# motor_controlboard.net
KiCad netlist of a schematic drawn in EAGLE
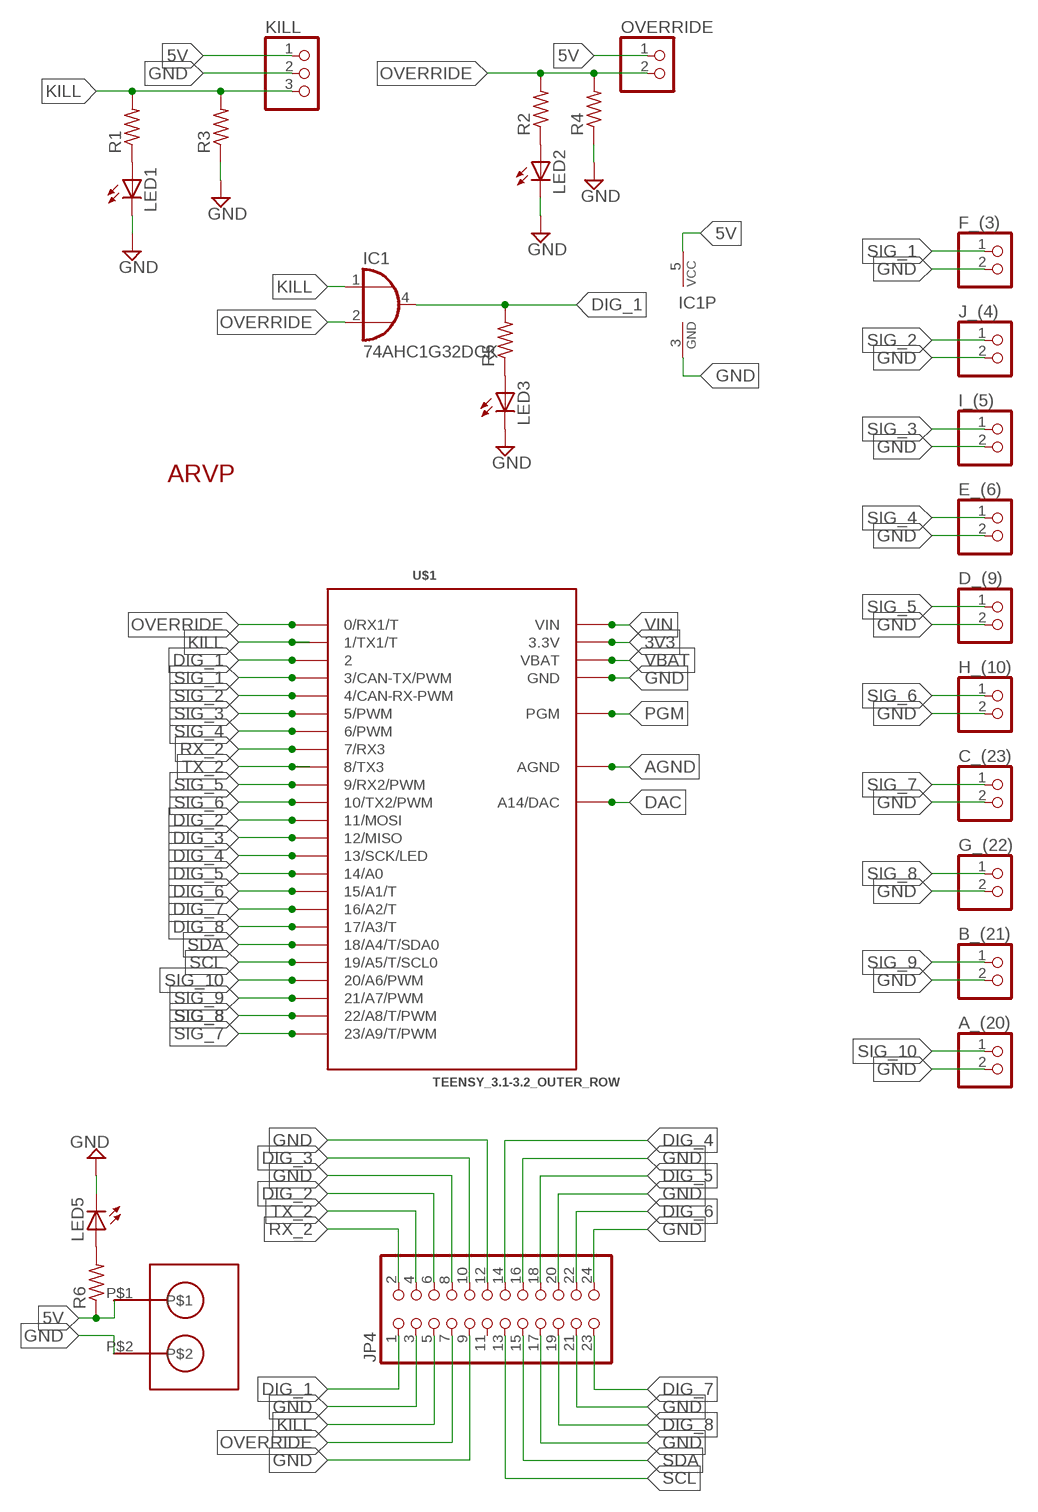
[diagram p0: schematic, sheet 1]

(export (version "E")
  (design (tool "Eeschema 10.0.6"))
  (components
    (comp (ref "A_(20)")
      (value "PINHD-1X2")
      (footprint "eagle-import:1X02")
      (libsource (lib "eagle-import") (part "PINHD-1X2"))
    )
    (comp (ref "B_(21)")
      (value "PINHD-1X2")
      (footprint "eagle-import:1X02")
      (libsource (lib "eagle-import") (part "PINHD-1X2"))
    )
    (comp (ref "C_(23)")
      (value "PINHD-1X2")
      (footprint "eagle-import:1X02")
      (libsource (lib "eagle-import") (part "PINHD-1X2"))
    )
    (comp (ref "D_(9)")
      (value "PINHD-1X2")
      (footprint "eagle-import:1X02")
      (libsource (lib "eagle-import") (part "PINHD-1X2"))
    )
    (comp (ref "E_(6)")
      (value "PINHD-1X2")
      (footprint "eagle-import:1X02")
      (libsource (lib "eagle-import") (part "PINHD-1X2"))
    )
    (comp (ref "F_(3)")
      (value "PINHD-1X2")
      (footprint "eagle-import:1X02")
      (libsource (lib "eagle-import") (part "PINHD-1X2"))
    )
    (comp (ref "G_(22)")
      (value "PINHD-1X2")
      (footprint "eagle-import:1X02")
      (libsource (lib "eagle-import") (part "PINHD-1X2"))
    )
    (comp (ref "H_(10)")
      (value "PINHD-1X2")
      (footprint "eagle-import:1X02")
      (libsource (lib "eagle-import") (part "PINHD-1X2"))
    )
    (comp (ref "IC1")
      (value "74AHC1G32DCK")
      (footprint "eagle-import:SC70-5")
      (libsource (lib "eagle-import") (part "741G32DCKAHC"))
    )
    (comp (ref "I_(5)")
      (value "PINHD-1X2")
      (footprint "eagle-import:1X02")
      (libsource (lib "eagle-import") (part "PINHD-1X2"))
    )
    (comp (ref "JP4")
      (value "PINHD-2X12")
      (footprint "eagle-import:2X12")
      (libsource (lib "eagle-import") (part "PINHD-2X12"))
    )
    (comp (ref "J_(4)")
      (value "PINHD-1X2")
      (footprint "eagle-import:1X02")
      (libsource (lib "eagle-import") (part "PINHD-1X2"))
    )
    (comp (ref "KILL")
      (value "PINHD-1X3")
      (footprint "eagle-import:1X03")
      (libsource (lib "eagle-import") (part "PINHD-1X3"))
    )
    (comp (ref "LED1")
      (value "LEDCHIP-LED0805")
      (footprint "eagle-import:CHIP-LED0805")
      (libsource (lib "eagle-import") (part "LEDCHIP-LED0805"))
    )
    (comp (ref "LED2")
      (value "LEDCHIP-LED0805")
      (footprint "eagle-import:CHIP-LED0805")
      (libsource (lib "eagle-import") (part "LEDCHIP-LED0805"))
    )
    (comp (ref "LED3")
      (value "LEDCHIP-LED0805")
      (footprint "eagle-import:CHIP-LED0805")
      (libsource (lib "eagle-import") (part "LEDCHIP-LED0805"))
    )
    (comp (ref "LED5")
      (value "LEDCHIP-LED0805")
      (footprint "eagle-import:CHIP-LED0805")
      (libsource (lib "eagle-import") (part "LEDCHIP-LED0805"))
    )
    (comp (ref "OVERRIDE")
      (value "PINHD-1X2")
      (footprint "eagle-import:1X02")
      (libsource (lib "eagle-import") (part "PINHD-1X2"))
    )
    (comp (ref "R1")
      (value "R-US_R0805")
      (footprint "eagle-import:R0805")
      (libsource (lib "eagle-import") (part "R-US_R0805"))
    )
    (comp (ref "R2")
      (value "R-US_R0805")
      (footprint "eagle-import:R0805")
      (libsource (lib "eagle-import") (part "R-US_R0805"))
    )
    (comp (ref "R3")
      (value "R-US_R0805")
      (footprint "eagle-import:R0805")
      (libsource (lib "eagle-import") (part "R-US_R0805"))
    )
    (comp (ref "R4")
      (value "R-US_R0805")
      (footprint "eagle-import:R0805")
      (libsource (lib "eagle-import") (part "R-US_R0805"))
    )
    (comp (ref "R5")
      (value "R-US_R0805")
      (footprint "eagle-import:R0805")
      (libsource (lib "eagle-import") (part "R-US_R0805"))
    )
    (comp (ref "R6")
      (value "R-US_R0805")
      (footprint "eagle-import:R0805")
      (libsource (lib "eagle-import") (part "R-US_R0805"))
    )
    (comp (ref "U$1")
      (value "TEENSY_3.1-3.2_OUTER_ROW")
      (footprint "eagle-import:TEENSY_3.0-3.2&LC_OUTER_ROW")
      (libsource (lib "eagle-import") (part "TEENSY_3.1-3.2_OUTER_ROW"))
    )
    (comp (ref "U$2")
      (value "ARVP_LOGO")
      (footprint "eagle-import:ARVP")
      (libsource (lib "eagle-import") (part "ARVP_LOGO"))
    )
    (comp (ref "U$3")
      (value "ARVP_MOLEX_FEMALE")
      (footprint "eagle-import:ARVP_MOLEX_FEMALE")
      (libsource (lib "eagle-import") (part "ARVP_MOLEX_FEMALE"))
    )
  )
  (nets
    (net (code "1") (name "3V3") (class "Default")
      (node (ref "U$1") (pin "3.3V") (pinfunction "3.3V_3.3V") (pintype "power_in"))
      (node (ref "U$1") (pin "3.3V1") (pinfunction "3.3V_3.3V1") (pintype "power_in"))
    )
    (net (code "2") (name "5V") (class "Default")
      (node (ref "IC1") (pin "5") (pinfunction "VCC_5") (pintype "power_in"))
      (node (ref "KILL") (pin "1") (pinfunction "1_1") (pintype "passive"))
      (node (ref "OVERRIDE") (pin "1") (pinfunction "1_1") (pintype "passive"))
      (node (ref "R6") (pin "1") (pinfunction "1_1") (pintype "passive"))
      (node (ref "U$3") (pin "P$1") (pinfunction "P$1_P$1") (pintype "bidirectional"))
    )
    (net (code "3") (name "AGND") (class "Default")
      (node (ref "U$1") (pin "AGND") (pinfunction "AGND_AGND") (pintype "power_in"))
    )
    (net (code "4") (name "DAC") (class "Default")
      (node (ref "U$1") (pin "RESET/DAC") (pinfunction "A14/DAC_RESET/DAC") (pintype "bidirectional"))
    )
    (net (code "5") (name "DIG_1") (class "Default")
      (node (ref "IC1") (pin "4") (pinfunction "O_4") (pintype "output"))
      (node (ref "JP4") (pin "1") (pinfunction "1_1") (pintype "passive"))
      (node (ref "R5") (pin "2") (pinfunction "2_2") (pintype "passive"))
      (node (ref "U$1") (pin "2") (pinfunction "2_2") (pintype "bidirectional"))
    )
    (net (code "6") (name "DIG_2") (class "Default")
      (node (ref "JP4") (pin "6") (pinfunction "6_6") (pintype "passive"))
      (node (ref "U$1") (pin "11") (pinfunction "11/MOSI_11") (pintype "bidirectional"))
    )
    (net (code "7") (name "DIG_3") (class "Default")
      (node (ref "JP4") (pin "10") (pinfunction "10_10") (pintype "passive"))
      (node (ref "U$1") (pin "12") (pinfunction "12/MISO_12") (pintype "bidirectional"))
    )
    (net (code "8") (name "DIG_4") (class "Default")
      (node (ref "JP4") (pin "14") (pinfunction "14_14") (pintype "passive"))
      (node (ref "U$1") (pin "13") (pinfunction "13/SCK/LED_13") (pintype "bidirectional"))
    )
    (net (code "9") (name "DIG_5") (class "Default")
      (node (ref "JP4") (pin "18") (pinfunction "18_18") (pintype "passive"))
      (node (ref "U$1") (pin "14/A0") (pinfunction "14/A0_14/A0") (pintype "bidirectional"))
    )
    (net (code "10") (name "DIG_6") (class "Default")
      (node (ref "JP4") (pin "22") (pinfunction "22_22") (pintype "passive"))
      (node (ref "U$1") (pin "15/A1") (pinfunction "15/A1/T_15/A1") (pintype "bidirectional"))
    )
    (net (code "11") (name "DIG_7") (class "Default")
      (node (ref "JP4") (pin "23") (pinfunction "23_23") (pintype "passive"))
      (node (ref "U$1") (pin "16/A2") (pinfunction "16/A2/T_16/A2") (pintype "bidirectional"))
    )
    (net (code "12") (name "DIG_8") (class "Default")
      (node (ref "JP4") (pin "19") (pinfunction "19_19") (pintype "passive"))
      (node (ref "U$1") (pin "17/A3") (pinfunction "17/A3/T_17/A3") (pintype "bidirectional"))
    )
    (net (code "13") (name "GND") (class "Default")
      (node (ref "A_(20)") (pin "2") (pinfunction "2_2") (pintype "passive"))
      (node (ref "B_(21)") (pin "2") (pinfunction "2_2") (pintype "passive"))
      (node (ref "C_(23)") (pin "2") (pinfunction "2_2") (pintype "passive"))
      (node (ref "D_(9)") (pin "2") (pinfunction "2_2") (pintype "passive"))
      (node (ref "E_(6)") (pin "2") (pinfunction "2_2") (pintype "passive"))
      (node (ref "F_(3)") (pin "2") (pinfunction "2_2") (pintype "passive"))
      (node (ref "G_(22)") (pin "2") (pinfunction "2_2") (pintype "passive"))
      (node (ref "H_(10)") (pin "2") (pinfunction "2_2") (pintype "passive"))
      (node (ref "IC1") (pin "3") (pinfunction "GND_3") (pintype "power_in"))
      (node (ref "I_(5)") (pin "2") (pinfunction "2_2") (pintype "passive"))
      (node (ref "JP4") (pin "12") (pinfunction "12_12") (pintype "passive"))
      (node (ref "JP4") (pin "16") (pinfunction "16_16") (pintype "passive"))
      (node (ref "JP4") (pin "17") (pinfunction "17_17") (pintype "passive"))
      (node (ref "JP4") (pin "20") (pinfunction "20_20") (pintype "passive"))
      (node (ref "JP4") (pin "21") (pinfunction "21_21") (pintype "passive"))
      (node (ref "JP4") (pin "24") (pinfunction "24_24") (pintype "passive"))
      (node (ref "JP4") (pin "3") (pinfunction "3_3") (pintype "passive"))
      (node (ref "JP4") (pin "8") (pinfunction "8_8") (pintype "passive"))
      (node (ref "JP4") (pin "9") (pinfunction "9_9") (pintype "passive"))
      (node (ref "J_(4)") (pin "2") (pinfunction "2_2") (pintype "passive"))
      (node (ref "KILL") (pin "2") (pinfunction "2_2") (pintype "passive"))
      (node (ref "LED1") (pin "C") (pinfunction "C_C") (pintype "passive"))
      (node (ref "LED2") (pin "C") (pinfunction "C_C") (pintype "passive"))
      (node (ref "LED3") (pin "C") (pinfunction "C_C") (pintype "passive"))
      (node (ref "LED5") (pin "C") (pinfunction "C_C") (pintype "passive"))
      (node (ref "R3") (pin "1") (pinfunction "1_1") (pintype "passive"))
      (node (ref "R4") (pin "1") (pinfunction "1_1") (pintype "passive"))
      (node (ref "U$1") (pin "GND") (pinfunction "GND_GND") (pintype "power_in"))
      (node (ref "U$1") (pin "GND1") (pinfunction "GND_GND1") (pintype "power_in"))
      (node (ref "U$3") (pin "P$2") (pinfunction "P$2_P$2") (pintype "bidirectional"))
    )
    (net (code "14") (name "KILL") (class "Default")
      (node (ref "IC1") (pin "1") (pinfunction "I0_1") (pintype "input"))
      (node (ref "JP4") (pin "5") (pinfunction "5_5") (pintype "passive"))
      (node (ref "KILL") (pin "3") (pinfunction "3_3") (pintype "passive"))
      (node (ref "R1") (pin "2") (pinfunction "2_2") (pintype "passive"))
      (node (ref "R3") (pin "2") (pinfunction "2_2") (pintype "passive"))
      (node (ref "U$1") (pin "1") (pinfunction "1/TX1/T_1") (pintype "bidirectional"))
    )
    (net (code "15") (name "Net-(LED1-PadA)") (class "Default")
      (node (ref "LED1") (pin "A") (pinfunction "A_A") (pintype "passive"))
      (node (ref "R1") (pin "1") (pinfunction "1_1") (pintype "passive"))
    )
    (net (code "16") (name "Net-(LED2-PadA)") (class "Default")
      (node (ref "LED2") (pin "A") (pinfunction "A_A") (pintype "passive"))
      (node (ref "R2") (pin "1") (pinfunction "1_1") (pintype "passive"))
    )
    (net (code "17") (name "Net-(LED3-PadA)") (class "Default")
      (node (ref "LED3") (pin "A") (pinfunction "A_A") (pintype "passive"))
      (node (ref "R5") (pin "1") (pinfunction "1_1") (pintype "passive"))
    )
    (net (code "18") (name "Net-(LED5-PadA)") (class "Default")
      (node (ref "LED5") (pin "A") (pinfunction "A_A") (pintype "passive"))
      (node (ref "R6") (pin "2") (pinfunction "2_2") (pintype "passive"))
    )
    (net (code "19") (name "OVERRIDE") (class "Default")
      (node (ref "IC1") (pin "2") (pinfunction "I1_2") (pintype "input"))
      (node (ref "JP4") (pin "7") (pinfunction "7_7") (pintype "passive"))
      (node (ref "OVERRIDE") (pin "2") (pinfunction "2_2") (pintype "passive"))
      (node (ref "R2") (pin "2") (pinfunction "2_2") (pintype "passive"))
      (node (ref "R4") (pin "2") (pinfunction "2_2") (pintype "passive"))
      (node (ref "U$1") (pin "0") (pinfunction "0/RX1/T_0") (pintype "bidirectional"))
    )
    (net (code "20") (name "PGM") (class "Default")
      (node (ref "U$1") (pin "PGM") (pinfunction "PGM_PGM") (pintype "bidirectional"))
    )
    (net (code "21") (name "RX_2") (class "Default")
      (node (ref "JP4") (pin "2") (pinfunction "2_2") (pintype "passive"))
      (node (ref "U$1") (pin "7") (pinfunction "7/RX3_7") (pintype "bidirectional"))
    )
    (net (code "22") (name "SCL") (class "Default")
      (node (ref "JP4") (pin "13") (pinfunction "13_13") (pintype "passive"))
      (node (ref "U$1") (pin "19/A5") (pinfunction "19/A5/T/SCL0_19/A5") (pintype "bidirectional"))
    )
    (net (code "23") (name "SDA") (class "Default")
      (node (ref "JP4") (pin "15") (pinfunction "15_15") (pintype "passive"))
      (node (ref "U$1") (pin "18/A4") (pinfunction "18/A4/T/SDA0_18/A4") (pintype "bidirectional"))
    )
    (net (code "24") (name "SIG_1") (class "Default")
      (node (ref "F_(3)") (pin "1") (pinfunction "1_1") (pintype "passive"))
      (node (ref "U$1") (pin "3") (pinfunction "3/CAN-TX/PWM_3") (pintype "bidirectional"))
    )
    (net (code "25") (name "SIG_2") (class "Default")
      (node (ref "J_(4)") (pin "1") (pinfunction "1_1") (pintype "passive"))
      (node (ref "U$1") (pin "4") (pinfunction "4/CAN-RX-PWM_4") (pintype "bidirectional"))
    )
    (net (code "26") (name "SIG_3") (class "Default")
      (node (ref "I_(5)") (pin "1") (pinfunction "1_1") (pintype "passive"))
      (node (ref "U$1") (pin "5") (pinfunction "5/PWM_5") (pintype "bidirectional"))
    )
    (net (code "27") (name "SIG_4") (class "Default")
      (node (ref "E_(6)") (pin "1") (pinfunction "1_1") (pintype "passive"))
      (node (ref "U$1") (pin "6") (pinfunction "6/PWM_6") (pintype "bidirectional"))
    )
    (net (code "28") (name "SIG_5") (class "Default")
      (node (ref "D_(9)") (pin "1") (pinfunction "1_1") (pintype "passive"))
      (node (ref "U$1") (pin "9") (pinfunction "9/RX2/PWM_9") (pintype "bidirectional"))
    )
    (net (code "29") (name "SIG_6") (class "Default")
      (node (ref "H_(10)") (pin "1") (pinfunction "1_1") (pintype "passive"))
      (node (ref "U$1") (pin "10") (pinfunction "10/TX2/PWM_10") (pintype "bidirectional"))
    )
    (net (code "30") (name "SIG_7") (class "Default")
      (node (ref "C_(23)") (pin "1") (pinfunction "1_1") (pintype "passive"))
      (node (ref "U$1") (pin "23/A9") (pinfunction "23/A9/T/PWM_23/A9") (pintype "bidirectional"))
    )
    (net (code "31") (name "SIG_8") (class "Default")
      (node (ref "G_(22)") (pin "1") (pinfunction "1_1") (pintype "passive"))
      (node (ref "U$1") (pin "22/A8") (pinfunction "22/A8/T/PWM_22/A8") (pintype "bidirectional"))
    )
    (net (code "32") (name "SIG_9") (class "Default")
      (node (ref "B_(21)") (pin "1") (pinfunction "1_1") (pintype "passive"))
      (node (ref "U$1") (pin "21/A7") (pinfunction "21/A7/PWM_21/A7") (pintype "bidirectional"))
    )
    (net (code "33") (name "SIG_10") (class "Default")
      (node (ref "A_(20)") (pin "1") (pinfunction "1_1") (pintype "passive"))
      (node (ref "U$1") (pin "20/A6") (pinfunction "20/A6/PWM_20/A6") (pintype "bidirectional"))
    )
    (net (code "34") (name "TX_2") (class "Default")
      (node (ref "JP4") (pin "4") (pinfunction "4_4") (pintype "passive"))
      (node (ref "U$1") (pin "8") (pinfunction "8/TX3_8") (pintype "bidirectional"))
    )
    (net (code "35") (name "VBAT") (class "Default")
      (node (ref "U$1") (pin "VBAT") (pinfunction "VBAT_VBAT") (pintype "power_in"))
    )
    (net (code "36") (name "VIN") (class "Default")
      (node (ref "U$1") (pin "VIN") (pinfunction "VIN_VIN") (pintype "power_in"))
    )
    (net (code "37") (name "unconnected-(JP4-Pad11)") (class "Default")
      (node (ref "JP4") (pin "11") (pinfunction "11_11") (pintype "passive"))
    )
  )
)
